# shelfControl.net
KiCad netlist of a schematic drawn in Altium Designer
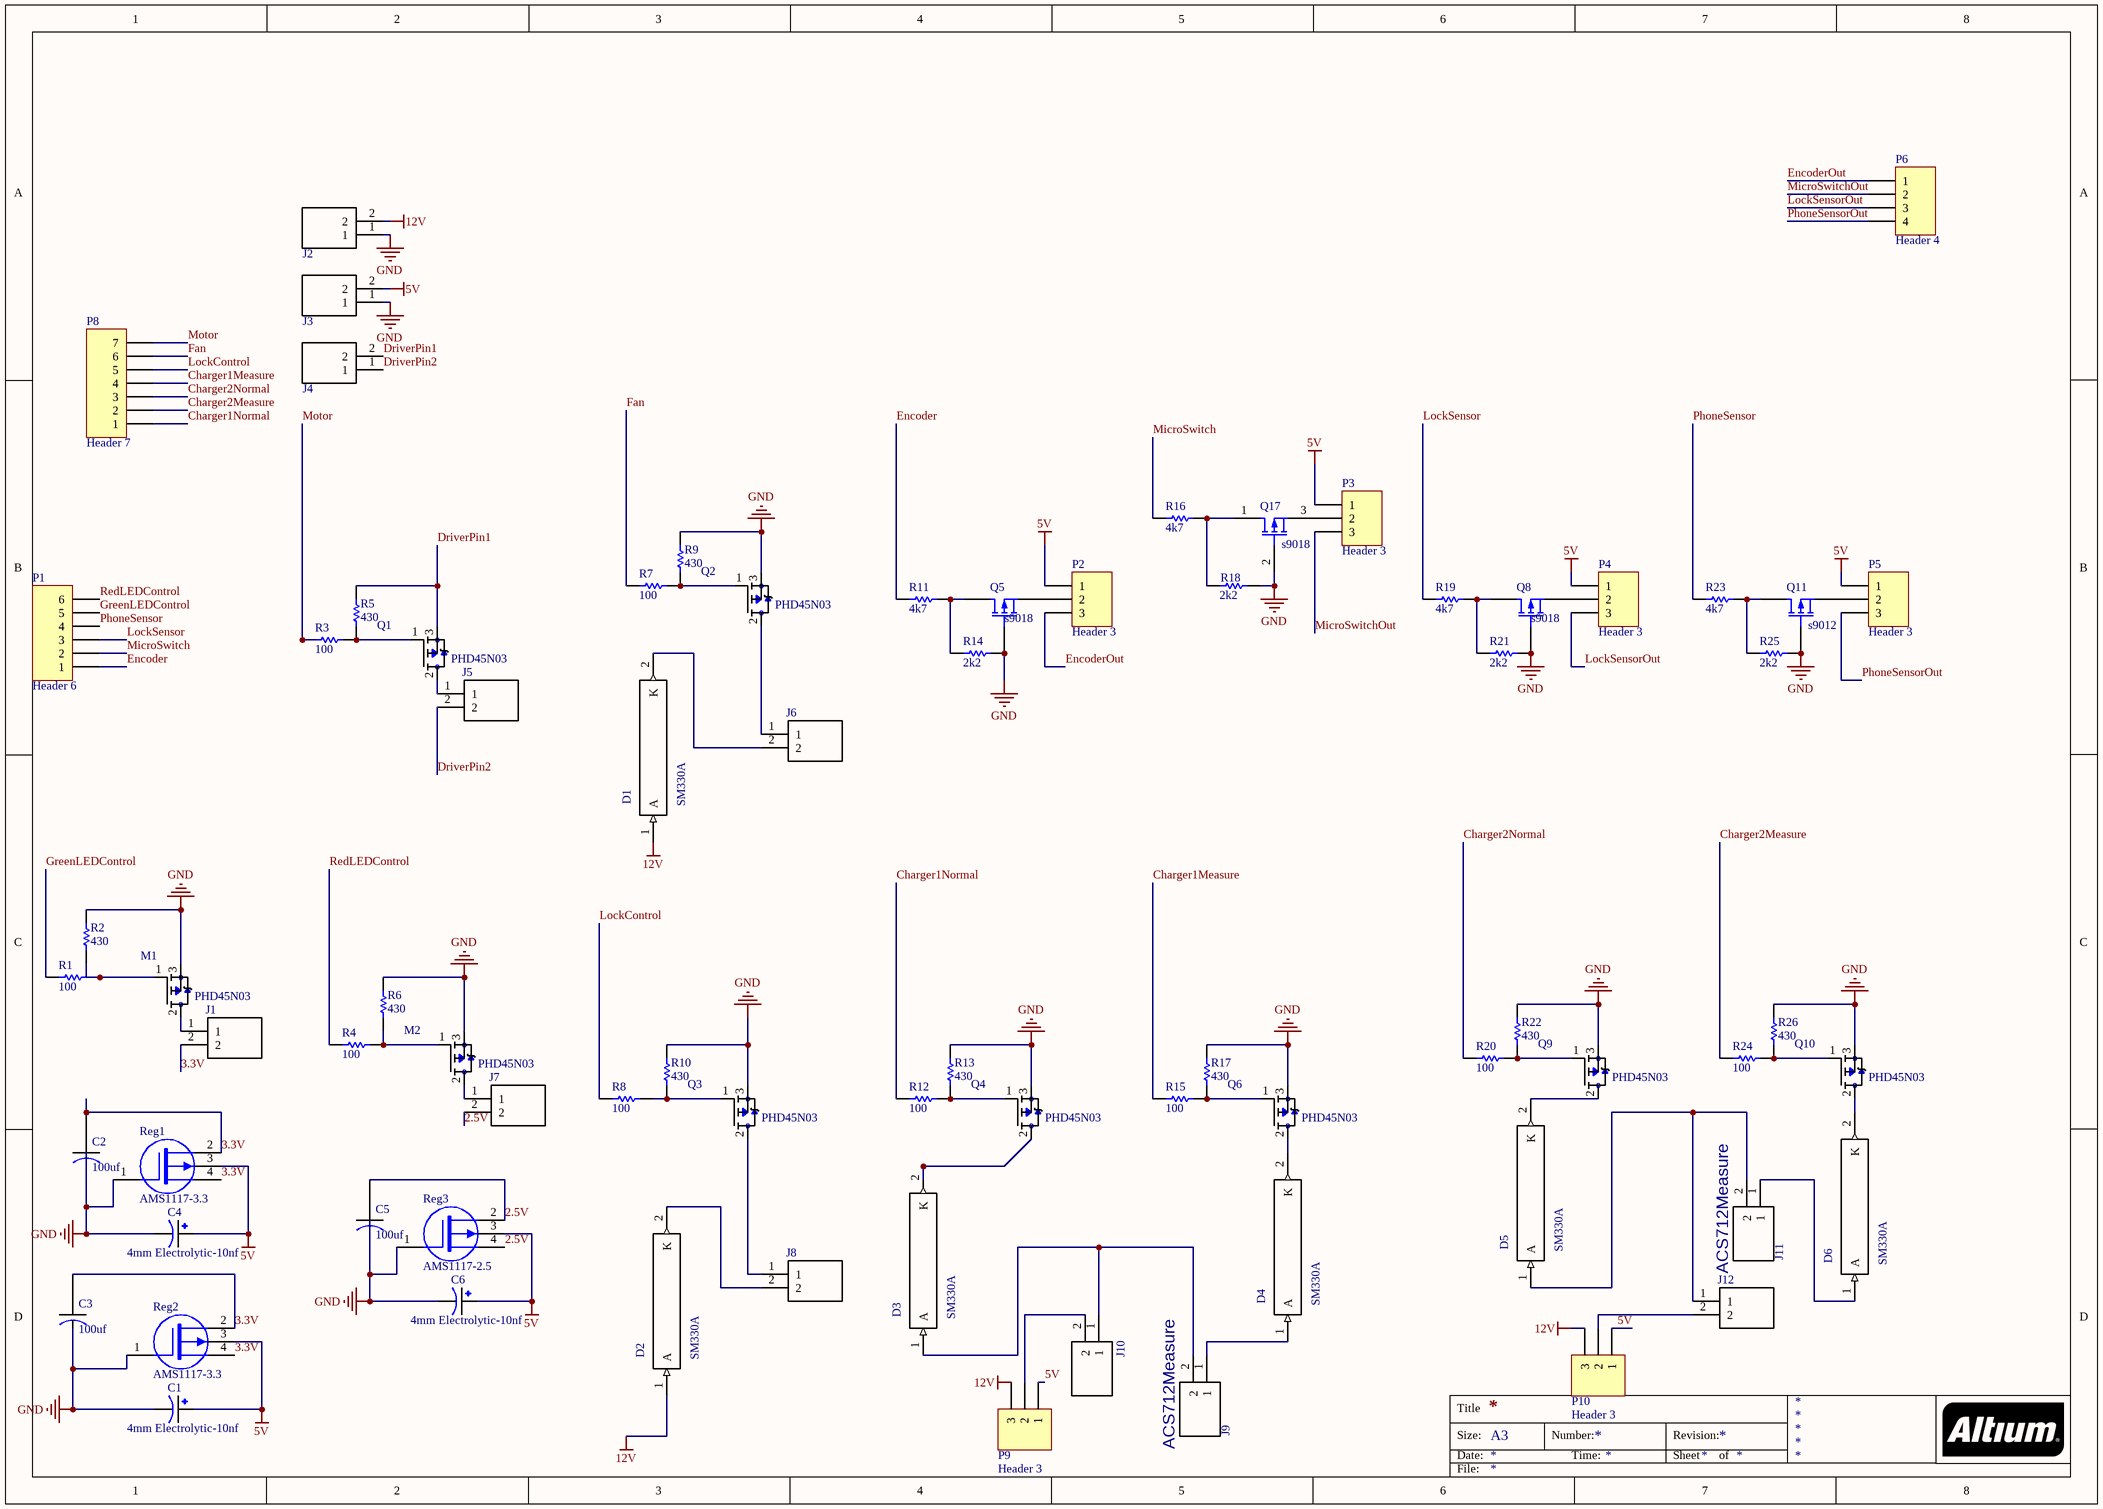
[diagram p0: shelfControl.SchDoc]

(export (version "E")
  (design (tool "Eeschema 10.0.6"))
  (components
    (comp (ref "C1")
      (value "4mm Electrolytic-10nf")
      (footprint "*CAP_EEE-FP1C100AR")
      (description "Electrolytic capacitor SMD 10 آµF 16 V 20 % _أک x L_ 4 mm x 5.8 mm Panasonic EEEFP1C100AR 1 pc_s_")
      (fields (field (name "MF") "Panasonic Electronic") (field (name "MP") "EEEFP1C100AR"))
      (libsource (lib "EEE-FP1C100AR") (part "EEE-FP1C100AR"))
    )
    (comp (ref "C2")
      (value "100uf")
      (footprint "*CAPAE0607X600N_16SVPC100M(Primary)")
      (description "SVPC Series 16 V 100 uF أک 6.3 x 5.9 mm Surface Mount Polymer Aluminum Capacitor")
      (fields (field (name "MF") "Panasonic") (field (name "MP") "16SVPC100M"))
      (libsource (lib "16SVPC100M") (part "16SVPC100M"))
    )
    (comp (ref "C3")
      (value "100uf")
      (footprint "*CAPAE0607X600N_16SVPC100M(Primary)")
      (description "SVPC Series 16 V 100 uF أک 6.3 x 5.9 mm Surface Mount Polymer Aluminum Capacitor")
      (fields (field (name "MF") "Panasonic") (field (name "MP") "16SVPC100M"))
      (libsource (lib "16SVPC100M") (part "16SVPC100M"))
    )
    (comp (ref "C4")
      (value "4mm Electrolytic-10nf")
      (footprint "*CAP_EEE-FP1C100AR")
      (description "Electrolytic capacitor SMD 10 آµF 16 V 20 % _أک x L_ 4 mm x 5.8 mm Panasonic EEEFP1C100AR 1 pc_s_")
      (fields (field (name "MF") "Panasonic Electronic") (field (name "MP") "EEEFP1C100AR"))
      (libsource (lib "EEE-FP1C100AR") (part "EEE-FP1C100AR"))
    )
    (comp (ref "C5")
      (value "100uf")
      (footprint "*CAPAE0607X600N_16SVPC100M(Primary)")
      (description "SVPC Series 16 V 100 uF أک 6.3 x 5.9 mm Surface Mount Polymer Aluminum Capacitor")
      (fields (field (name "MF") "Panasonic") (field (name "MP") "16SVPC100M"))
      (libsource (lib "16SVPC100M") (part "16SVPC100M"))
    )
    (comp (ref "C6")
      (value "4mm Electrolytic-10nf")
      (footprint "*CAP_EEE-FP1C100AR")
      (description "Electrolytic capacitor SMD 10 آµF 16 V 20 % _أک x L_ 4 mm x 5.8 mm Panasonic EEEFP1C100AR 1 pc_s_")
      (fields (field (name "MF") "Panasonic Electronic") (field (name "MP") "EEEFP1C100AR"))
      (libsource (lib "EEE-FP1C100AR") (part "EEE-FP1C100AR"))
    )
    (comp (ref "D1")
      (value "SM330A")
      (footprint "*DIOM5227X270N_S1M(Primary)")
      (description "SCHOTTKY RECTIFIER 2A; Voltage Vrrm: 60V; Diode Case Style: DO-214AC; Case Style: DO-214AC")
      (fields (field (name "MF") "STMicroelectronics") (field (name "MP") "STPS2L60A"))
      (libsource (lib "STPS2L60A") (part "STPS2L60A"))
    )
    (comp (ref "D2")
      (value "SM330A")
      (footprint "*DIOM5227X270N_S1M(Primary)")
      (description "SCHOTTKY RECTIFIER 2A; Voltage Vrrm: 60V; Diode Case Style: DO-214AC; Case Style: DO-214AC")
      (fields (field (name "MF") "STMicroelectronics") (field (name "MP") "STPS2L60A"))
      (libsource (lib "STPS2L60A") (part "STPS2L60A"))
    )
    (comp (ref "D3")
      (value "SM330A")
      (footprint "*DIOM5227X270N_S1M(Primary)")
      (description "SCHOTTKY RECTIFIER 2A; Voltage Vrrm: 60V; Diode Case Style: DO-214AC; Case Style: DO-214AC")
      (fields (field (name "MF") "STMicroelectronics") (field (name "MP") "STPS2L60A"))
      (libsource (lib "STPS2L60A") (part "STPS2L60A"))
    )
    (comp (ref "D4")
      (value "SM330A")
      (footprint "*DIOM5227X270N_S1M(Primary)")
      (description "SCHOTTKY RECTIFIER 2A; Voltage Vrrm: 60V; Diode Case Style: DO-214AC; Case Style: DO-214AC")
      (fields (field (name "MF") "STMicroelectronics") (field (name "MP") "STPS2L60A"))
      (libsource (lib "STPS2L60A") (part "STPS2L60A"))
    )
    (comp (ref "D5")
      (value "SM330A")
      (footprint "*DIOM5227X270N_S1M(Primary)")
      (description "SCHOTTKY RECTIFIER 2A; Voltage Vrrm: 60V; Diode Case Style: DO-214AC; Case Style: DO-214AC")
      (fields (field (name "MF") "STMicroelectronics") (field (name "MP") "STPS2L60A"))
      (libsource (lib "STPS2L60A") (part "STPS2L60A"))
    )
    (comp (ref "D6")
      (value "SM330A")
      (footprint "*DIOM5227X270N_S1M(Primary)")
      (description "SCHOTTKY RECTIFIER 2A; Voltage Vrrm: 60V; Diode Case Style: DO-214AC; Case Style: DO-214AC")
      (fields (field (name "MF") "STMicroelectronics") (field (name "MP") "STPS2L60A"))
      (libsource (lib "STPS2L60A") (part "STPS2L60A"))
    )
    (comp (ref "J1")
      (value "6-1123723-2")
      (footprint "*TE_6-1123723-2")
      (description "3.96 EP HDR ASSY 2P_GREEN_")
      (fields (field (name "MF") "TE Connectivity"))
      (libsource (lib "6-1123723-2") (part "6-1123723-2"))
    )
    (comp (ref "J2")
      (value "6-1123723-2")
      (footprint "*TE_6-1123723-2")
      (description "3.96 EP HDR ASSY 2P_GREEN_")
      (fields (field (name "MF") "TE Connectivity"))
      (libsource (lib "6-1123723-2") (part "6-1123723-2"))
    )
    (comp (ref "J3")
      (value "6-1123723-2")
      (footprint "*TE_6-1123723-2")
      (description "3.96 EP HDR ASSY 2P_GREEN_")
      (fields (field (name "MF") "TE Connectivity"))
      (libsource (lib "6-1123723-2") (part "6-1123723-2"))
    )
    (comp (ref "J4")
      (value "6-1123723-2")
      (footprint "*TE_6-1123723-2")
      (description "3.96 EP HDR ASSY 2P_GREEN_")
      (fields (field (name "MF") "TE Connectivity"))
      (libsource (lib "6-1123723-2") (part "6-1123723-2"))
    )
    (comp (ref "J5")
      (value "6-1123723-2")
      (footprint "*TE_6-1123723-2")
      (description "3.96 EP HDR ASSY 2P_GREEN_")
      (fields (field (name "MF") "TE Connectivity"))
      (libsource (lib "6-1123723-2") (part "6-1123723-2"))
    )
    (comp (ref "J6")
      (value "6-1123723-2")
      (footprint "*TE_6-1123723-2")
      (description "3.96 EP HDR ASSY 2P_GREEN_")
      (fields (field (name "MF") "TE Connectivity"))
      (libsource (lib "6-1123723-2") (part "6-1123723-2"))
    )
    (comp (ref "J7")
      (value "6-1123723-2")
      (footprint "*TE_6-1123723-2")
      (description "3.96 EP HDR ASSY 2P_GREEN_")
      (fields (field (name "MF") "TE Connectivity"))
      (libsource (lib "6-1123723-2") (part "6-1123723-2"))
    )
    (comp (ref "J8")
      (value "6-1123723-2")
      (footprint "*TE_6-1123723-2")
      (description "3.96 EP HDR ASSY 2P_GREEN_")
      (fields (field (name "MF") "TE Connectivity"))
      (libsource (lib "6-1123723-2") (part "6-1123723-2"))
    )
    (comp (ref "J9")
      (value "ACS712Measure")
      (footprint "*TE_6-1123723-2")
      (description "3.96 EP HDR ASSY 2P_GREEN_")
      (fields (field (name "MF") "TE Connectivity") (field (name "MP") "6-1123723-2"))
      (libsource (lib "6-1123723-2") (part "6-1123723-2"))
    )
    (comp (ref "J10")
      (value "6-1123723-2")
      (footprint "*TE_6-1123723-2")
      (description "3.96 EP HDR ASSY 2P_GREEN_")
      (fields (field (name "MF") "TE Connectivity"))
      (libsource (lib "6-1123723-2") (part "6-1123723-2"))
    )
    (comp (ref "J11")
      (value "ACS712Measure")
      (footprint "*TE_6-1123723-2")
      (description "3.96 EP HDR ASSY 2P_GREEN_")
      (fields (field (name "MF") "TE Connectivity") (field (name "MP") "6-1123723-2"))
      (libsource (lib "6-1123723-2") (part "6-1123723-2"))
    )
    (comp (ref "J12")
      (value "6-1123723-2")
      (footprint "*TE_6-1123723-2")
      (description "3.96 EP HDR ASSY 2P_GREEN_")
      (fields (field (name "MF") "TE Connectivity"))
      (libsource (lib "6-1123723-2") (part "6-1123723-2"))
    )
    (comp (ref "M1")
      (value "PHD45N03")
      (footprint "*DPAK228P998X235-3N")
      (description "P-Channel 40 V 10.6 mOhm OptiMOSآ®-P2 Power-Transistor -PG-TO-252-3")
      (fields (field (name "MP") "IPD50P04P4L-11") (field (name "MF") "Infineon Technologies"))
      (libsource (lib "IPD50P04P4L-11") (part "IPD50P04P4L-11"))
    )
    (comp (ref "M2")
      (value "PHD45N03")
      (footprint "*DPAK228P998X235-3N")
      (description "P-Channel 40 V 10.6 mOhm OptiMOSآ®-P2 Power-Transistor -PG-TO-252-3")
      (fields (field (name "MP") "IPD50P04P4L-11") (field (name "MF") "Infineon Technologies"))
      (libsource (lib "IPD50P04P4L-11") (part "IPD50P04P4L-11"))
    )
    (comp (ref "P1")
      (value "Header 6")
      (footprint "HDR1X6")
      (description "Header, 6-Pin")
      (fields (field (name "PUBLISHER") "Altium Limited"))
      (libsource (lib "Miscellaneous Connectors") (part "Header 6"))
    )
    (comp (ref "P2")
      (value "Header 3")
      (footprint "HDR1X3")
      (description "Header, 3-Pin")
      (fields (field (name "PUBLISHER") "Altium Limited"))
      (libsource (lib "") (part "Header 3_1"))
    )
    (comp (ref "P3")
      (value "Header 3")
      (footprint "HDR1X3")
      (description "Header, 3-Pin")
      (fields (field (name "PUBLISHER") "Altium Limited"))
      (libsource (lib "") (part "Header 3_1"))
    )
    (comp (ref "P4")
      (value "Header 3")
      (footprint "HDR1X3")
      (description "Header, 3-Pin")
      (fields (field (name "PUBLISHER") "Altium Limited"))
      (libsource (lib "") (part "Header 3_1"))
    )
    (comp (ref "P5")
      (value "Header 3")
      (footprint "HDR1X3")
      (description "Header, 3-Pin")
      (fields (field (name "PUBLISHER") "Altium Limited"))
      (libsource (lib "") (part "Header 3_1"))
    )
    (comp (ref "P6")
      (value "Header 4")
      (footprint "HDR1X4")
      (description "Header, 4-Pin")
      (fields (field (name "PUBLISHER") "Altium Limited"))
      (libsource (lib "Miscellaneous Connectors") (part "Header 4"))
    )
    (comp (ref "P8")
      (value "Header 7")
      (footprint "HDR1X7")
      (description "Header, 7-Pin")
      (fields (field (name "PUBLISHER") "Altium Limited"))
      (libsource (lib "Miscellaneous Connectors") (part "Header 7"))
    )
    (comp (ref "P9")
      (value "Header 3")
      (footprint "HDR1X3")
      (description "Header, 3-Pin")
      (fields (field (name "PUBLISHER") "Altium Limited"))
      (libsource (lib "Miscellaneous Connectors") (part "Header 3"))
    )
    (comp (ref "P10")
      (value "Header 3")
      (footprint "HDR1X3")
      (description "Header, 3-Pin")
      (fields (field (name "PUBLISHER") "Altium Limited"))
      (libsource (lib "Miscellaneous Connectors") (part "Header 3"))
    )
    (comp (ref "Q1")
      (value "PHD45N03")
      (footprint "*DPAK228P998X235-3N")
      (description "P-Channel 40 V 10.6 mOhm OptiMOSآ®-P2 Power-Transistor -PG-TO-252-3")
      (fields (field (name "MP") "IPD50P04P4L-11") (field (name "MF") "Infineon Technologies"))
      (libsource (lib "IPD50P04P4L-11") (part "IPD50P04P4L-11"))
    )
    (comp (ref "Q2")
      (value "PHD45N03")
      (footprint "*DPAK228P998X235-3N")
      (description "P-Channel 40 V 10.6 mOhm OptiMOSآ®-P2 Power-Transistor -PG-TO-252-3")
      (fields (field (name "MP") "IPD50P04P4L-11") (field (name "MF") "Infineon Technologies"))
      (libsource (lib "IPD50P04P4L-11") (part "IPD50P04P4L-11"))
    )
    (comp (ref "Q3")
      (value "PHD45N03")
      (footprint "*DPAK228P998X235-3N")
      (description "P-Channel 40 V 10.6 mOhm OptiMOSآ®-P2 Power-Transistor -PG-TO-252-3")
      (fields (field (name "MP") "IPD50P04P4L-11") (field (name "MF") "Infineon Technologies"))
      (libsource (lib "IPD50P04P4L-11") (part "IPD50P04P4L-11"))
    )
    (comp (ref "Q4")
      (value "PHD45N03")
      (footprint "*DPAK228P998X235-3N")
      (description "P-Channel 40 V 10.6 mOhm OptiMOSآ®-P2 Power-Transistor -PG-TO-252-3")
      (fields (field (name "MP") "IPD50P04P4L-11") (field (name "MF") "Infineon Technologies"))
      (libsource (lib "IPD50P04P4L-11") (part "IPD50P04P4L-11"))
    )
    (comp (ref "Q5")
      (value "s9018")
      (footprint "SOT-23_N")
      (description "P-Channel MOSFET")
      (fields (field (name "PUBLISHER") "Altium Limited"))
      (libsource (lib "Miscellaneous Devices") (part "MOSFET-P"))
    )
    (comp (ref "Q6")
      (value "PHD45N03")
      (footprint "*DPAK228P998X235-3N")
      (description "P-Channel 40 V 10.6 mOhm OptiMOSآ®-P2 Power-Transistor -PG-TO-252-3")
      (fields (field (name "MP") "IPD50P04P4L-11") (field (name "MF") "Infineon Technologies"))
      (libsource (lib "IPD50P04P4L-11") (part "IPD50P04P4L-11"))
    )
    (comp (ref "Q8")
      (value "s9018")
      (footprint "SOT-23_N")
      (description "P-Channel MOSFET")
      (fields (field (name "PUBLISHER") "Altium Limited"))
      (libsource (lib "Miscellaneous Devices") (part "MOSFET-P"))
    )
    (comp (ref "Q9")
      (value "PHD45N03")
      (footprint "*DPAK228P998X235-3N")
      (description "P-Channel 40 V 10.6 mOhm OptiMOSآ®-P2 Power-Transistor -PG-TO-252-3")
      (fields (field (name "MP") "IPD50P04P4L-11") (field (name "MF") "Infineon Technologies"))
      (libsource (lib "IPD50P04P4L-11") (part "IPD50P04P4L-11"))
    )
    (comp (ref "Q10")
      (value "PHD45N03")
      (footprint "*DPAK228P998X235-3N")
      (description "P-Channel 40 V 10.6 mOhm OptiMOSآ®-P2 Power-Transistor -PG-TO-252-3")
      (fields (field (name "MP") "IPD50P04P4L-11") (field (name "MF") "Infineon Technologies"))
      (libsource (lib "IPD50P04P4L-11") (part "IPD50P04P4L-11"))
    )
    (comp (ref "Q11")
      (value "s9012")
      (footprint "SOT-23_N")
      (description "P-Channel MOSFET")
      (fields (field (name "PUBLISHER") "Altium Limited"))
      (libsource (lib "Miscellaneous Devices") (part "MOSFET-P"))
    )
    (comp (ref "Q17")
      (value "s9018")
      (footprint "SOT-23_N")
      (description "P-Channel MOSFET")
      (fields (field (name "PUBLISHER") "Altium Limited"))
      (libsource (lib "") (part "MOSFET-P_1"))
    )
    (comp (ref "R1")
      (value "100")
      (footprint "6-0805_L")
      (description "Resistor")
      (fields (field (name "Comment") "R100") (field (name "PUBLISHER") "Altium Limited"))
      (libsource (lib "Miscellaneous Devices") (part "Res1"))
    )
    (comp (ref "R2")
      (value "430")
      (footprint "6-0805_L")
      (description "Resistor")
      (fields (field (name "Comment") "R430") (field (name "PUBLISHER") "Altium Limited"))
      (libsource (lib "Miscellaneous Devices") (part "Res1"))
    )
    (comp (ref "R3")
      (value "100")
      (footprint "6-0805_L")
      (description "Resistor")
      (fields (field (name "Comment") "R100") (field (name "PUBLISHER") "Altium Limited"))
      (libsource (lib "Miscellaneous Devices") (part "Res1"))
    )
    (comp (ref "R4")
      (value "100")
      (footprint "6-0805_L")
      (description "Resistor")
      (fields (field (name "Comment") "R100") (field (name "PUBLISHER") "Altium Limited"))
      (libsource (lib "Miscellaneous Devices") (part "Res1"))
    )
    (comp (ref "R5")
      (value "430")
      (footprint "6-0805_L")
      (description "Resistor")
      (fields (field (name "Comment") "R430") (field (name "PUBLISHER") "Altium Limited"))
      (libsource (lib "Miscellaneous Devices") (part "Res1"))
    )
    (comp (ref "R6")
      (value "430")
      (footprint "6-0805_L")
      (description "Resistor")
      (fields (field (name "Comment") "R430") (field (name "PUBLISHER") "Altium Limited"))
      (libsource (lib "Miscellaneous Devices") (part "Res1"))
    )
    (comp (ref "R7")
      (value "100")
      (footprint "6-0805_L")
      (description "Resistor")
      (fields (field (name "Comment") "R100") (field (name "PUBLISHER") "Altium Limited"))
      (libsource (lib "Miscellaneous Devices") (part "Res1"))
    )
    (comp (ref "R8")
      (value "100")
      (footprint "6-0805_L")
      (description "Resistor")
      (fields (field (name "Comment") "R100") (field (name "PUBLISHER") "Altium Limited"))
      (libsource (lib "Miscellaneous Devices") (part "Res1"))
    )
    (comp (ref "R9")
      (value "430")
      (footprint "6-0805_L")
      (description "Resistor")
      (fields (field (name "Comment") "R430") (field (name "PUBLISHER") "Altium Limited"))
      (libsource (lib "Miscellaneous Devices") (part "Res1"))
    )
    (comp (ref "R10")
      (value "430")
      (footprint "6-0805_L")
      (description "Resistor")
      (fields (field (name "Comment") "R430") (field (name "PUBLISHER") "Altium Limited"))
      (libsource (lib "Miscellaneous Devices") (part "Res1"))
    )
    (comp (ref "R11")
      (value "4k7")
      (footprint "6-0805_L")
      (description "Resistor")
      (fields (field (name "Comment") "R4k7") (field (name "PUBLISHER") "Altium Limited"))
      (libsource (lib "Miscellaneous Devices") (part "Res1"))
    )
    (comp (ref "R12")
      (value "100")
      (footprint "6-0805_L")
      (description "Resistor")
      (fields (field (name "Comment") "R100") (field (name "PUBLISHER") "Altium Limited"))
      (libsource (lib "Miscellaneous Devices") (part "Res1"))
    )
    (comp (ref "R13")
      (value "430")
      (footprint "6-0805_L")
      (description "Resistor")
      (fields (field (name "Comment") "R430") (field (name "PUBLISHER") "Altium Limited"))
      (libsource (lib "Miscellaneous Devices") (part "Res1"))
    )
    (comp (ref "R14")
      (value "2k2")
      (footprint "6-0805_L")
      (description "Resistor")
      (fields (field (name "Comment") "R2k2") (field (name "PUBLISHER") "Altium Limited"))
      (libsource (lib "Miscellaneous Devices") (part "Res1"))
    )
    (comp (ref "R15")
      (value "100")
      (footprint "6-0805_L")
      (description "Resistor")
      (fields (field (name "Comment") "R100") (field (name "PUBLISHER") "Altium Limited"))
      (libsource (lib "Miscellaneous Devices") (part "Res1"))
    )
    (comp (ref "R16")
      (value "4k7")
      (footprint "6-0805_L")
      (description "Resistor")
      (fields (field (name "Comment") "R4k7") (field (name "PUBLISHER") "Altium Limited"))
      (libsource (lib "Miscellaneous Devices") (part "Res1"))
    )
    (comp (ref "R17")
      (value "430")
      (footprint "6-0805_L")
      (description "Resistor")
      (fields (field (name "Comment") "R430") (field (name "PUBLISHER") "Altium Limited"))
      (libsource (lib "Miscellaneous Devices") (part "Res1"))
    )
    (comp (ref "R18")
      (value "2k2")
      (footprint "6-0805_L")
      (description "Resistor")
      (fields (field (name "Comment") "R2k2") (field (name "PUBLISHER") "Altium Limited"))
      (libsource (lib "Miscellaneous Devices") (part "Res1"))
    )
    (comp (ref "R19")
      (value "4k7")
      (footprint "6-0805_L")
      (description "Resistor")
      (fields (field (name "Comment") "R4k7") (field (name "PUBLISHER") "Altium Limited"))
      (libsource (lib "Miscellaneous Devices") (part "Res1"))
    )
    (comp (ref "R20")
      (value "100")
      (footprint "6-0805_L")
      (description "Resistor")
      (fields (field (name "Comment") "R100") (field (name "PUBLISHER") "Altium Limited"))
      (libsource (lib "Miscellaneous Devices") (part "Res1"))
    )
    (comp (ref "R21")
      (value "2k2")
      (footprint "6-0805_L")
      (description "Resistor")
      (fields (field (name "Comment") "R2k2") (field (name "PUBLISHER") "Altium Limited"))
      (libsource (lib "Miscellaneous Devices") (part "Res1"))
    )
    (comp (ref "R22")
      (value "430")
      (footprint "6-0805_L")
      (description "Resistor")
      (fields (field (name "Comment") "R430") (field (name "PUBLISHER") "Altium Limited"))
      (libsource (lib "Miscellaneous Devices") (part "Res1"))
    )
    (comp (ref "R23")
      (value "4k7")
      (footprint "6-0805_L")
      (description "Resistor")
      (fields (field (name "Comment") "R4k7") (field (name "PUBLISHER") "Altium Limited"))
      (libsource (lib "Miscellaneous Devices") (part "Res1"))
    )
    (comp (ref "R24")
      (value "100")
      (footprint "6-0805_L")
      (description "Resistor")
      (fields (field (name "Comment") "R100") (field (name "PUBLISHER") "Altium Limited"))
      (libsource (lib "Miscellaneous Devices") (part "Res1"))
    )
    (comp (ref "R25")
      (value "2k2")
      (footprint "6-0805_L")
      (description "Resistor")
      (fields (field (name "Comment") "R2k2") (field (name "PUBLISHER") "Altium Limited"))
      (libsource (lib "Miscellaneous Devices") (part "Res1"))
    )
    (comp (ref "R26")
      (value "430")
      (footprint "6-0805_L")
      (description "Resistor")
      (fields (field (name "Comment") "R430") (field (name "PUBLISHER") "Altium Limited"))
      (libsource (lib "Miscellaneous Devices") (part "Res1"))
    )
    (comp (ref "Reg1")
      (value "AMS1117-3.3")
      (footprint "SOT223_N")
      (description "P-Channel MOSFET, Externally Terminated Substrate")
      (fields (field (name "PUBLISHER") "Altium Limited"))
      (libsource (lib "Miscellaneous Devices") (part "MOSFET-P4"))
    )
    (comp (ref "Reg2")
      (value "AMS1117-3.3")
      (footprint "SOT223_N")
      (description "P-Channel MOSFET, Externally Terminated Substrate")
      (fields (field (name "PUBLISHER") "Altium Limited"))
      (libsource (lib "Miscellaneous Devices") (part "MOSFET-P4"))
    )
    (comp (ref "Reg3")
      (value "AMS1117-2.5")
      (footprint "SOT223_N")
      (description "P-Channel MOSFET, Externally Terminated Substrate")
      (fields (field (name "PUBLISHER") "Altium Limited"))
      (libsource (lib "Miscellaneous Devices") (part "MOSFET-P4"))
    )
  )
  (nets
    (net (code "1") (name "/2.5V") (class "Default")
      (node (ref "C5") (pin "POS") (pinfunction "POS_POS") (pintype "passive"))
      (node (ref "J7") (pin "2") (pinfunction "2_2") (pintype "passive"))
      (node (ref "Reg3") (pin "2") (pinfunction "D_2") (pintype "passive"))
      (node (ref "Reg3") (pin "4") (pinfunction "S_4") (pintype "passive"))
    )
    (net (code "2") (name "/3.3V") (class "Default")
      (node (ref "C2") (pin "POS") (pinfunction "POS_POS") (pintype "passive"))
      (node (ref "C3") (pin "POS") (pinfunction "POS_POS") (pintype "passive"))
      (node (ref "J1") (pin "2") (pinfunction "2_2") (pintype "passive"))
      (node (ref "Reg1") (pin "2") (pinfunction "D_2") (pintype "passive"))
      (node (ref "Reg1") (pin "4") (pinfunction "S_4") (pintype "passive"))
      (node (ref "Reg2") (pin "2") (pinfunction "D_2") (pintype "passive"))
      (node (ref "Reg2") (pin "4") (pinfunction "S_4") (pintype "passive"))
    )
    (net (code "3") (name "/Charger1Measure") (class "Default")
      (node (ref "P8") (pin "4") (pinfunction "4_4") (pintype "passive"))
      (node (ref "R15") (pin "1") (pinfunction "1_1") (pintype "passive"))
    )
    (net (code "4") (name "/Charger1Normal") (class "Default")
      (node (ref "P8") (pin "1") (pinfunction "1_1") (pintype "passive"))
      (node (ref "R12") (pin "1") (pinfunction "1_1") (pintype "passive"))
    )
    (net (code "5") (name "/Charger2Measure") (class "Default")
      (node (ref "P8") (pin "2") (pinfunction "2_2") (pintype "passive"))
      (node (ref "R24") (pin "1") (pinfunction "1_1") (pintype "passive"))
    )
    (net (code "6") (name "/Charger2Normal") (class "Default")
      (node (ref "P8") (pin "3") (pinfunction "3_3") (pintype "passive"))
      (node (ref "R20") (pin "1") (pinfunction "1_1") (pintype "passive"))
    )
    (net (code "7") (name "/DriverPin1") (class "Default")
      (node (ref "J4") (pin "2") (pinfunction "2_2") (pintype "passive"))
      (node (ref "Q1") (pin "3") (pinfunction "S_3") (pintype "passive"))
      (node (ref "R5") (pin "1") (pinfunction "1_1") (pintype "passive"))
    )
    (net (code "8") (name "/DriverPin2") (class "Default")
      (node (ref "J4") (pin "1") (pinfunction "1_1") (pintype "passive"))
      (node (ref "J5") (pin "2") (pinfunction "2_2") (pintype "passive"))
    )
    (net (code "9") (name "/Encoder") (class "Default")
      (node (ref "P1") (pin "1") (pinfunction "1_1") (pintype "passive"))
      (node (ref "R11") (pin "1") (pinfunction "1_1") (pintype "passive"))
    )
    (net (code "10") (name "/EncoderOut") (class "Default")
      (node (ref "P2") (pin "3") (pinfunction "3_3") (pintype "passive"))
      (node (ref "P6") (pin "1") (pinfunction "1_1") (pintype "passive"))
    )
    (net (code "11") (name "/Fan") (class "Default")
      (node (ref "P8") (pin "6") (pinfunction "6_6") (pintype "passive"))
      (node (ref "R7") (pin "1") (pinfunction "1_1") (pintype "passive"))
    )
    (net (code "12") (name "/GreenLEDControl") (class "Default")
      (node (ref "P1") (pin "5") (pinfunction "5_5") (pintype "passive"))
      (node (ref "R1") (pin "1") (pinfunction "1_1") (pintype "passive"))
    )
    (net (code "13") (name "/LockControl") (class "Default")
      (node (ref "P8") (pin "5") (pinfunction "5_5") (pintype "passive"))
      (node (ref "R8") (pin "1") (pinfunction "1_1") (pintype "passive"))
    )
    (net (code "14") (name "/LockSensor") (class "Default")
      (node (ref "P1") (pin "3") (pinfunction "3_3") (pintype "passive"))
      (node (ref "R19") (pin "1") (pinfunction "1_1") (pintype "passive"))
    )
    (net (code "15") (name "/LockSensorOut") (class "Default")
      (node (ref "P4") (pin "3") (pinfunction "3_3") (pintype "passive"))
      (node (ref "P6") (pin "3") (pinfunction "3_3") (pintype "passive"))
    )
    (net (code "16") (name "/MicroSwitch") (class "Default")
      (node (ref "P1") (pin "2") (pinfunction "2_2") (pintype "passive"))
      (node (ref "R16") (pin "2") (pinfunction "2_2") (pintype "passive"))
    )
    (net (code "17") (name "/MicroSwitchOut") (class "Default")
      (node (ref "P3") (pin "3") (pinfunction "3_3") (pintype "passive"))
      (node (ref "P6") (pin "2") (pinfunction "2_2") (pintype "passive"))
    )
    (net (code "18") (name "/Motor") (class "Default")
      (node (ref "P8") (pin "7") (pinfunction "7_7") (pintype "passive"))
      (node (ref "R3") (pin "1") (pinfunction "1_1") (pintype "passive"))
    )
    (net (code "19") (name "/PhoneSensor") (class "Default")
      (node (ref "P1") (pin "4") (pinfunction "4_4") (pintype "passive"))
      (node (ref "R23") (pin "1") (pinfunction "1_1") (pintype "passive"))
    )
    (net (code "20") (name "/PhoneSensorOut") (class "Default")
      (node (ref "P5") (pin "3") (pinfunction "3_3") (pintype "passive"))
      (node (ref "P6") (pin "4") (pinfunction "4_4") (pintype "passive"))
    )
    (net (code "21") (name "/RedLEDControl") (class "Default")
      (node (ref "P1") (pin "6") (pinfunction "6_6") (pintype "passive"))
      (node (ref "R4") (pin "1") (pinfunction "1_1") (pintype "passive"))
    )
    (net (code "22") (name "5V") (class "Default")
      (node (ref "C1") (pin "1") (pinfunction "1_1") (pintype "passive"))
      (node (ref "C4") (pin "1") (pinfunction "1_1") (pintype "passive"))
      (node (ref "C6") (pin "1") (pinfunction "1_1") (pintype "passive"))
      (node (ref "J3") (pin "2") (pinfunction "2_2") (pintype "passive"))
      (node (ref "P10") (pin "1") (pinfunction "1_1") (pintype "passive"))
      (node (ref "P2") (pin "1") (pinfunction "1_1") (pintype "passive"))
      (node (ref "P3") (pin "1") (pinfunction "1_1") (pintype "passive"))
      (node (ref "P4") (pin "1") (pinfunction "1_1") (pintype "passive"))
      (node (ref "P5") (pin "1") (pinfunction "1_1") (pintype "passive"))
      (node (ref "P9") (pin "1") (pinfunction "1_1") (pintype "passive"))
      (node (ref "Reg1") (pin "3") (pinfunction "U_3") (pintype "passive"))
      (node (ref "Reg2") (pin "3") (pinfunction "U_3") (pintype "passive"))
      (node (ref "Reg3") (pin "3") (pinfunction "U_3") (pintype "passive"))
    )
    (net (code "23") (name "12V") (class "Default")
      (node (ref "D1") (pin "1") (pinfunction "A_1") (pintype "input"))
      (node (ref "D2") (pin "1") (pinfunction "A_1") (pintype "input"))
      (node (ref "J2") (pin "2") (pinfunction "2_2") (pintype "passive"))
      (node (ref "P10") (pin "3") (pinfunction "3_3") (pintype "passive"))
      (node (ref "P9") (pin "3") (pinfunction "3_3") (pintype "passive"))
    )
    (net (code "24") (name "GND") (class "Default")
      (node (ref "C1") (pin "2") (pinfunction "2_2") (pintype "passive"))
      (node (ref "C2") (pin "NEG") (pinfunction "NEG_NEG") (pintype "passive"))
      (node (ref "C3") (pin "NEG") (pinfunction "NEG_NEG") (pintype "passive"))
      (node (ref "C4") (pin "2") (pinfunction "2_2") (pintype "passive"))
      (node (ref "C5") (pin "NEG") (pinfunction "NEG_NEG") (pintype "passive"))
      (node (ref "C6") (pin "2") (pinfunction "2_2") (pintype "passive"))
      (node (ref "J2") (pin "1") (pinfunction "1_1") (pintype "passive"))
      (node (ref "J3") (pin "1") (pinfunction "1_1") (pintype "passive"))
      (node (ref "M1") (pin "3") (pinfunction "S_3") (pintype "passive"))
      (node (ref "M2") (pin "3") (pinfunction "S_3") (pintype "passive"))
      (node (ref "Q10") (pin "3") (pinfunction "S_3") (pintype "passive"))
      (node (ref "Q11") (pin "2") (pinfunction "G_2") (pintype "passive"))
      (node (ref "Q17") (pin "2") (pinfunction "G_2") (pintype "passive"))
      (node (ref "Q2") (pin "3") (pinfunction "S_3") (pintype "passive"))
      (node (ref "Q3") (pin "3") (pinfunction "S_3") (pintype "passive"))
      (node (ref "Q4") (pin "3") (pinfunction "S_3") (pintype "passive"))
      (node (ref "Q5") (pin "2") (pinfunction "G_2") (pintype "passive"))
      (node (ref "Q6") (pin "3") (pinfunction "S_3") (pintype "passive"))
      (node (ref "Q8") (pin "2") (pinfunction "G_2") (pintype "passive"))
      (node (ref "Q9") (pin "3") (pinfunction "S_3") (pintype "passive"))
      (node (ref "R10") (pin "1") (pinfunction "1_1") (pintype "passive"))
      (node (ref "R13") (pin "1") (pinfunction "1_1") (pintype "passive"))
      (node (ref "R14") (pin "2") (pinfunction "2_2") (pintype "passive"))
      (node (ref "R17") (pin "1") (pinfunction "1_1") (pintype "passive"))
      (node (ref "R18") (pin "1") (pinfunction "1_1") (pintype "passive"))
      (node (ref "R2") (pin "1") (pinfunction "1_1") (pintype "passive"))
      (node (ref "R21") (pin "2") (pinfunction "2_2") (pintype "passive"))
      (node (ref "R22") (pin "1") (pinfunction "1_1") (pintype "passive"))
      (node (ref "R25") (pin "2") (pinfunction "2_2") (pintype "passive"))
      (node (ref "R26") (pin "1") (pinfunction "1_1") (pintype "passive"))
      (node (ref "R6") (pin "1") (pinfunction "1_1") (pintype "passive"))
      (node (ref "R9") (pin "1") (pinfunction "1_1") (pintype "passive"))
      (node (ref "Reg1") (pin "1") (pinfunction "G_1") (pintype "passive"))
      (node (ref "Reg2") (pin "1") (pinfunction "G_1") (pintype "passive"))
      (node (ref "Reg3") (pin "1") (pinfunction "G_1") (pintype "passive"))
    )
    (net (code "25") (name "Net-(D1-K)") (class "Default")
      (node (ref "D1") (pin "2") (pinfunction "K_2") (pintype "output"))
      (node (ref "J6") (pin "2") (pinfunction "2_2") (pintype "passive"))
    )
    (net (code "26") (name "Net-(D2-K)") (class "Default")
      (node (ref "D2") (pin "2") (pinfunction "K_2") (pintype "output"))
      (node (ref "J8") (pin "2") (pinfunction "2_2") (pintype "passive"))
    )
    (net (code "27") (name "Net-(D3-A)") (class "Default")
      (node (ref "D3") (pin "1") (pinfunction "A_1") (pintype "input"))
      (node (ref "J10") (pin "1") (pinfunction "1_1") (pintype "passive"))
      (node (ref "J9") (pin "2") (pinfunction "2_2") (pintype "passive"))
    )
    (net (code "28") (name "Net-(D3-K)") (class "Default")
      (node (ref "D3") (pin "2") (pinfunction "K_2") (pintype "output"))
      (node (ref "Q4") (pin "2") (pinfunction "D_2") (pintype "passive"))
    )
    (net (code "29") (name "Net-(D4-A)") (class "Default")
      (node (ref "D4") (pin "1") (pinfunction "A_1") (pintype "input"))
      (node (ref "J9") (pin "1") (pinfunction "1_1") (pintype "passive"))
    )
    (net (code "30") (name "Net-(D4-K)") (class "Default")
      (node (ref "D4") (pin "2") (pinfunction "K_2") (pintype "output"))
      (node (ref "Q6") (pin "2") (pinfunction "D_2") (pintype "passive"))
    )
    (net (code "31") (name "Net-(D5-A)") (class "Default")
      (node (ref "D5") (pin "1") (pinfunction "A_1") (pintype "input"))
      (node (ref "J11") (pin "2") (pinfunction "2_2") (pintype "passive"))
      (node (ref "J12") (pin "1") (pinfunction "1_1") (pintype "passive"))
    )
    (net (code "32") (name "Net-(D5-K)") (class "Default")
      (node (ref "D5") (pin "2") (pinfunction "K_2") (pintype "output"))
      (node (ref "Q9") (pin "2") (pinfunction "D_2") (pintype "passive"))
    )
    (net (code "33") (name "Net-(D6-A)") (class "Default")
      (node (ref "D6") (pin "1") (pinfunction "A_1") (pintype "input"))
      (node (ref "J11") (pin "1") (pinfunction "1_1") (pintype "passive"))
    )
    (net (code "34") (name "Net-(D6-K)") (class "Default")
      (node (ref "D6") (pin "2") (pinfunction "K_2") (pintype "output"))
      (node (ref "Q10") (pin "2") (pinfunction "D_2") (pintype "passive"))
    )
    (net (code "35") (name "Net-(J10-Pad2)") (class "Default")
      (node (ref "J10") (pin "2") (pinfunction "2_2") (pintype "passive"))
      (node (ref "P9") (pin "2") (pinfunction "2_2") (pintype "passive"))
    )
    (net (code "36") (name "Net-(J12-Pad2)") (class "Default")
      (node (ref "J12") (pin "2") (pinfunction "2_2") (pintype "passive"))
      (node (ref "P10") (pin "2") (pinfunction "2_2") (pintype "passive"))
    )
    (net (code "37") (name "Net-(M1-D)") (class "Default")
      (node (ref "J1") (pin "1") (pinfunction "1_1") (pintype "passive"))
      (node (ref "M1") (pin "2") (pinfunction "D_2") (pintype "passive"))
    )
    (net (code "38") (name "Net-(M1-G)") (class "Default")
      (node (ref "M1") (pin "1") (pinfunction "G_1") (pintype "passive"))
      (node (ref "R1") (pin "2") (pinfunction "2_2") (pintype "passive"))
      (node (ref "R2") (pin "2") (pinfunction "2_2") (pintype "passive"))
    )
    (net (code "39") (name "Net-(M2-D)") (class "Default")
      (node (ref "J7") (pin "1") (pinfunction "1_1") (pintype "passive"))
      (node (ref "M2") (pin "2") (pinfunction "D_2") (pintype "passive"))
    )
    (net (code "40") (name "Net-(M2-G)") (class "Default")
      (node (ref "M2") (pin "1") (pinfunction "G_1") (pintype "passive"))
      (node (ref "R4") (pin "2") (pinfunction "2_2") (pintype "passive"))
      (node (ref "R6") (pin "2") (pinfunction "2_2") (pintype "passive"))
    )
    (net (code "41") (name "Net-(Q1-D)") (class "Default")
      (node (ref "J5") (pin "1") (pinfunction "1_1") (pintype "passive"))
      (node (ref "Q1") (pin "2") (pinfunction "D_2") (pintype "passive"))
    )
    (net (code "42") (name "Net-(Q1-G)") (class "Default")
      (node (ref "Q1") (pin "1") (pinfunction "G_1") (pintype "passive"))
      (node (ref "R3") (pin "2") (pinfunction "2_2") (pintype "passive"))
      (node (ref "R5") (pin "2") (pinfunction "2_2") (pintype "passive"))
    )
    (net (code "43") (name "Net-(Q2-D)") (class "Default")
      (node (ref "J6") (pin "1") (pinfunction "1_1") (pintype "passive"))
      (node (ref "Q2") (pin "2") (pinfunction "D_2") (pintype "passive"))
    )
    (net (code "44") (name "Net-(Q2-G)") (class "Default")
      (node (ref "Q2") (pin "1") (pinfunction "G_1") (pintype "passive"))
      (node (ref "R7") (pin "2") (pinfunction "2_2") (pintype "passive"))
      (node (ref "R9") (pin "2") (pinfunction "2_2") (pintype "passive"))
    )
    (net (code "45") (name "Net-(Q3-D)") (class "Default")
      (node (ref "J8") (pin "1") (pinfunction "1_1") (pintype "passive"))
      (node (ref "Q3") (pin "2") (pinfunction "D_2") (pintype "passive"))
    )
    (net (code "46") (name "Net-(Q3-G)") (class "Default")
      (node (ref "Q3") (pin "1") (pinfunction "G_1") (pintype "passive"))
      (node (ref "R10") (pin "2") (pinfunction "2_2") (pintype "passive"))
      (node (ref "R8") (pin "2") (pinfunction "2_2") (pintype "passive"))
    )
    (net (code "47") (name "Net-(Q4-G)") (class "Default")
      (node (ref "Q4") (pin "1") (pinfunction "G_1") (pintype "passive"))
      (node (ref "R12") (pin "2") (pinfunction "2_2") (pintype "passive"))
      (node (ref "R13") (pin "2") (pinfunction "2_2") (pintype "passive"))
    )
    (net (code "48") (name "Net-(Q5-D)") (class "Default")
      (node (ref "Q5") (pin "1") (pinfunction "D_1") (pintype "passive"))
      (node (ref "R11") (pin "2") (pinfunction "2_2") (pintype "passive"))
      (node (ref "R14") (pin "1") (pinfunction "1_1") (pintype "passive"))
    )
    (net (code "49") (name "Net-(Q5-S)") (class "Default")
      (node (ref "P2") (pin "2") (pinfunction "2_2") (pintype "passive"))
      (node (ref "Q5") (pin "3") (pinfunction "S_3") (pintype "passive"))
    )
    (net (code "50") (name "Net-(Q6-G)") (class "Default")
      (node (ref "Q6") (pin "1") (pinfunction "G_1") (pintype "passive"))
      (node (ref "R15") (pin "2") (pinfunction "2_2") (pintype "passive"))
      (node (ref "R17") (pin "2") (pinfunction "2_2") (pintype "passive"))
    )
    (net (code "51") (name "Net-(Q8-D)") (class "Default")
      (node (ref "Q8") (pin "1") (pinfunction "D_1") (pintype "passive"))
      (node (ref "R19") (pin "2") (pinfunction "2_2") (pintype "passive"))
      (node (ref "R21") (pin "1") (pinfunction "1_1") (pintype "passive"))
    )
    (net (code "52") (name "Net-(Q8-S)") (class "Default")
      (node (ref "P4") (pin "2") (pinfunction "2_2") (pintype "passive"))
      (node (ref "Q8") (pin "3") (pinfunction "S_3") (pintype "passive"))
    )
    (net (code "53") (name "Net-(Q9-G)") (class "Default")
      (node (ref "Q9") (pin "1") (pinfunction "G_1") (pintype "passive"))
      (node (ref "R20") (pin "2") (pinfunction "2_2") (pintype "passive"))
      (node (ref "R22") (pin "2") (pinfunction "2_2") (pintype "passive"))
    )
    (net (code "54") (name "Net-(Q10-G)") (class "Default")
      (node (ref "Q10") (pin "1") (pinfunction "G_1") (pintype "passive"))
      (node (ref "R24") (pin "2") (pinfunction "2_2") (pintype "passive"))
      (node (ref "R26") (pin "2") (pinfunction "2_2") (pintype "passive"))
    )
    (net (code "55") (name "Net-(Q11-D)") (class "Default")
      (node (ref "Q11") (pin "1") (pinfunction "D_1") (pintype "passive"))
      (node (ref "R23") (pin "2") (pinfunction "2_2") (pintype "passive"))
      (node (ref "R25") (pin "1") (pinfunction "1_1") (pintype "passive"))
    )
    (net (code "56") (name "Net-(Q11-S)") (class "Default")
      (node (ref "P5") (pin "2") (pinfunction "2_2") (pintype "passive"))
      (node (ref "Q11") (pin "3") (pinfunction "S_3") (pintype "passive"))
    )
    (net (code "57") (name "Net-(Q17-D)") (class "Default")
      (node (ref "Q17") (pin "1") (pinfunction "D_1") (pintype "passive"))
      (node (ref "R16") (pin "1") (pinfunction "1_1") (pintype "passive"))
      (node (ref "R18") (pin "2") (pinfunction "2_2") (pintype "passive"))
    )
    (net (code "58") (name "Net-(Q17-S)") (class "Default")
      (node (ref "P3") (pin "2") (pinfunction "2_2") (pintype "passive"))
      (node (ref "Q17") (pin "3") (pinfunction "S_3") (pintype "passive"))
    )
  )
)
